# MegaShieldTrio.net
KiCad netlist of a schematic drawn in EAGLE
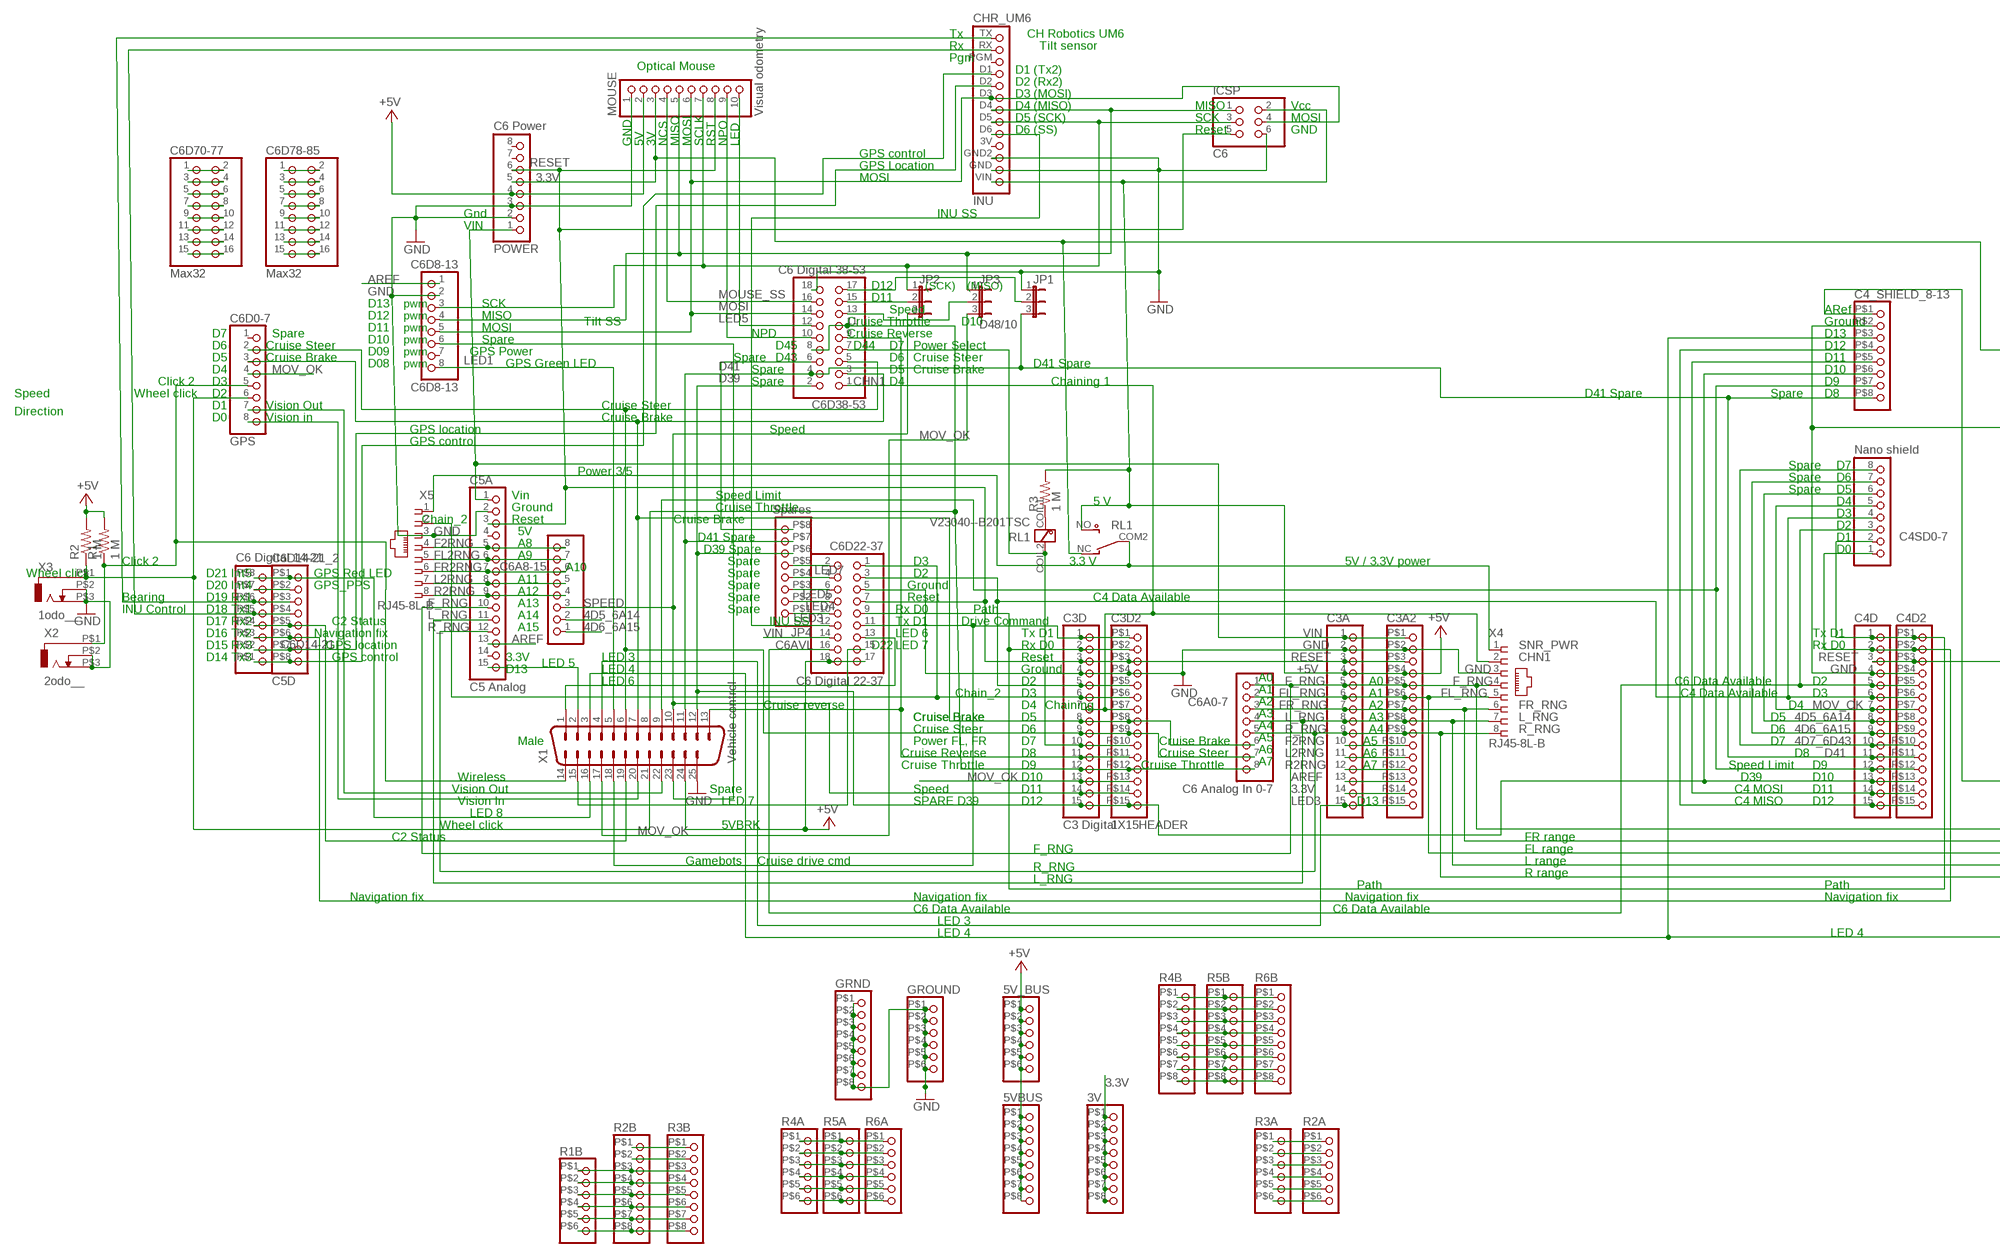
[diagram p0: schematic, sheet 1, part 1 of 2]
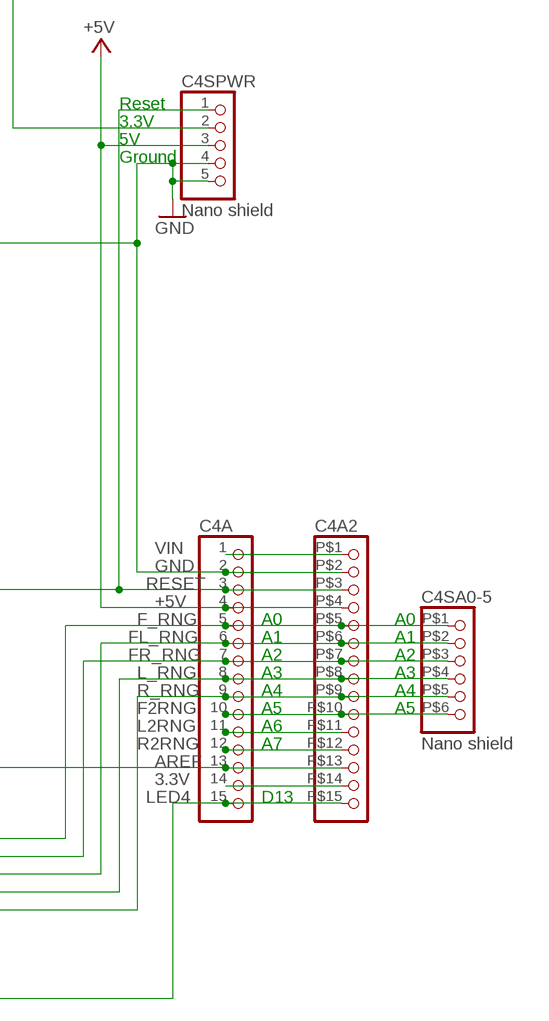
[diagram p1: schematic, sheet 1, part 2 of 2]

(export (version "E")
  (design (tool "Eeschema 10.0.6"))
  (components
    (comp (ref "3V")
      (value "PINHD-1X8SMALL8")
      (footprint "eagle-import:1X8HEADER")
      (libsource (lib "eagle-import") (part "PINHD-1X8SMALL8"))
    )
    (comp (ref "5VBUS")
      (value "PINHD-1X8SMALL8")
      (footprint "eagle-import:1X8HEADER")
      (libsource (lib "eagle-import") (part "PINHD-1X8SMALL8"))
    )
    (comp (ref "5V_BUS")
      (value "1X6HEADER")
      (footprint "eagle-import:1X6HEADER")
      (libsource (lib "eagle-import") (part "1X6HEADER"))
    )
    (comp (ref "C3A")
      (value "PINHD-1X15")
      (footprint "eagle-import:1X15")
      (libsource (lib "eagle-import") (part "PINHD-1X15"))
    )
    (comp (ref "C3A2")
      (value "1X15HEADER")
      (footprint "eagle-import:1X15HEADER")
      (libsource (lib "eagle-import") (part "1X15HEADER"))
    )
    (comp (ref "C3D")
      (value "C3 Digital")
      (footprint "eagle-import:1X15")
      (libsource (lib "eagle-import") (part "PINHD-1X15"))
    )
    (comp (ref "C3D2")
      (value "1X15HEADER")
      (footprint "eagle-import:1X15HEADER")
      (libsource (lib "eagle-import") (part "1X15HEADER"))
    )
    (comp (ref "C4A")
      (value "PINHD-1X15")
      (footprint "eagle-import:1X15")
      (libsource (lib "eagle-import") (part "PINHD-1X15"))
    )
    (comp (ref "C4A2")
      (value "1X15HEADER")
      (footprint "eagle-import:1X15HEADER")
      (libsource (lib "eagle-import") (part "1X15HEADER"))
    )
    (comp (ref "C4D")
      (value "PINHD-1X15")
      (footprint "eagle-import:1X15")
      (libsource (lib "eagle-import") (part "PINHD-1X15"))
    )
    (comp (ref "C4D2")
      (value "1X15HEADER")
      (footprint "eagle-import:1X15HEADER")
      (libsource (lib "eagle-import") (part "1X15HEADER"))
    )
    (comp (ref "C4SA0-5")
      (value "Nano shield")
      (footprint "eagle-import:1X6HEADER")
      (libsource (lib "eagle-import") (part "1X6HEADER"))
    )
    (comp (ref "C4SD0-7")
      (value "Nano shield")
      (footprint "eagle-import:1X08")
      (libsource (lib "eagle-import") (part "pinhead_PINHD-1X8"))
    )
    (comp (ref "C4SPWR")
      (value "Nano shield")
      (footprint "eagle-import:1X05")
      (libsource (lib "eagle-import") (part "PINHD-1X5"))
    )
    (comp (ref "C4_SHIELD_8-13")
      (value "PINHD-1X8SMALL8")
      (footprint "eagle-import:1X8HEADER")
      (libsource (lib "eagle-import") (part "PINHD-1X8SMALL8"))
    )
    (comp (ref "C5A")
      (value "C5 Analog")
      (footprint "eagle-import:1X15")
      (libsource (lib "eagle-import") (part "PINHD-1X15"))
    )
    (comp (ref "C6A0-7")
      (value "C6 Analog In 0-7")
      (footprint "eagle-import:1X08")
      (libsource (lib "eagle-import") (part "pinhead_PINHD-1X8"))
    )
    (comp (ref "C6A8-15")
      (value "PINHD-1X8")
      (footprint "eagle-import:1X08")
      (libsource (lib "eagle-import") (part "pinhead_PINHD-1X8"))
    )
    (comp (ref "C6D0-7")
      (value "GPS")
      (footprint "eagle-import:1X08")
      (libsource (lib "eagle-import") (part "pinhead_PINHD-1X8"))
    )
    (comp (ref "C6D8-13")
      (value "C6D8-13")
      (footprint "eagle-import:1X08")
      (libsource (lib "eagle-import") (part "pinhead_PINHD-1X8"))
    )
    (comp (ref "C6D14-21")
      (value "C6 Digital 14-21")
      (footprint "eagle-import:1X8HEADER")
      (libsource (lib "eagle-import") (part "PINHD-1X8SMALL8"))
    )
    (comp (ref "C6D14-21_2")
      (value "C5D")
      (footprint "eagle-import:1X8HEADER")
      (libsource (lib "eagle-import") (part "PINHD-1X8SMALL8"))
    )
    (comp (ref "C6D22-37")
      (value "C6 Digital 22-37")
      (footprint "eagle-import:2X09")
      (libsource (lib "eagle-import") (part "PINHD-2X9"))
    )
    (comp (ref "C6D38-53")
      (value "C6 Digital 38-53")
      (footprint "eagle-import:2X09")
      (libsource (lib "eagle-import") (part "PINHD-2X9"))
    )
    (comp (ref "C6D70-77")
      (value "Max32")
      (footprint "eagle-import:2X08")
      (libsource (lib "eagle-import") (part "PINHD-2X8"))
    )
    (comp (ref "C6D78-85")
      (value "Max32")
      (footprint "eagle-import:2X08")
      (libsource (lib "eagle-import") (part "PINHD-2X8"))
    )
    (comp (ref "GRND")
      (value "PINHD-1X8SMALL8")
      (footprint "eagle-import:1X8HEADER")
      (libsource (lib "eagle-import") (part "PINHD-1X8SMALL8"))
    )
    (comp (ref "GROUND")
      (value "1X6HEADER")
      (footprint "eagle-import:1X6HEADER")
      (libsource (lib "eagle-import") (part "1X6HEADER"))
    )
    (comp (ref "ICSP")
      (value "C6")
      (footprint "eagle-import:2X03")
      (libsource (lib "eagle-import") (part "PINHD-2X3"))
    )
    (comp (ref "INU")
      (value "CHR_UM6")
      (footprint "eagle-import:CHR_UM6")
      (libsource (lib "eagle-import") (part "CHR_UM6"))
    )
    (comp (ref "JP1")
      (value "JP2E")
      (footprint "eagle-import:JP2")
      (libsource (lib "eagle-import") (part "JP2E"))
    )
    (comp (ref "JP2")
      (value "JP2E")
      (footprint "eagle-import:JP2")
      (libsource (lib "eagle-import") (part "JP2E"))
    )
    (comp (ref "JP3")
      (value "D48/10")
      (footprint "eagle-import:JP2")
      (libsource (lib "eagle-import") (part "JP2E"))
    )
    (comp (ref "JP4")
      (value "Spares")
      (footprint "eagle-import:1X8HEADER")
      (libsource (lib "eagle-import") (part "PINHD-1X8SMALL8"))
    )
    (comp (ref "MOUSE")
      (value "Visual odometry")
      (footprint "eagle-import:1X10")
      (libsource (lib "eagle-import") (part "PINHD-1X10"))
    )
    (comp (ref "POWER")
      (value "C6 Power")
      (footprint "eagle-import:1X08")
      (libsource (lib "eagle-import") (part "pinhead_PINHD-1X8"))
    )
    (comp (ref "R1")
      (value "1 M")
      (footprint "eagle-import:0207_10")
      (libsource (lib "eagle-import") (part "R-US_0207/10"))
    )
    (comp (ref "R1B")
      (value "1X6HEADER")
      (footprint "eagle-import:1X6HEADER")
      (libsource (lib "eagle-import") (part "1X6HEADER"))
    )
    (comp (ref "R2")
      (value "1 M")
      (footprint "eagle-import:0207_10")
      (libsource (lib "eagle-import") (part "R-US_0207/10"))
    )
    (comp (ref "R2A")
      (value "1X6HEADER")
      (footprint "eagle-import:1X6HEADER")
      (libsource (lib "eagle-import") (part "1X6HEADER"))
    )
    (comp (ref "R2B")
      (value "PINHD-1X8SMALL8")
      (footprint "eagle-import:1X8HEADER")
      (libsource (lib "eagle-import") (part "PINHD-1X8SMALL8"))
    )
    (comp (ref "R3")
      (value "1 M")
      (footprint "eagle-import:0207_10")
      (libsource (lib "eagle-import") (part "R-US_0207/10"))
    )
    (comp (ref "R3A")
      (value "1X6HEADER")
      (footprint "eagle-import:1X6HEADER")
      (libsource (lib "eagle-import") (part "1X6HEADER"))
    )
    (comp (ref "R3B")
      (value "PINHD-1X8SMALL8")
      (footprint "eagle-import:1X8HEADER")
      (libsource (lib "eagle-import") (part "PINHD-1X8SMALL8"))
    )
    (comp (ref "R4A")
      (value "1X6HEADER")
      (footprint "eagle-import:1X6HEADER")
      (libsource (lib "eagle-import") (part "1X6HEADER"))
    )
    (comp (ref "R4B")
      (value "PINHD-1X8SMALL8")
      (footprint "eagle-import:1X8HEADER")
      (libsource (lib "eagle-import") (part "PINHD-1X8SMALL8"))
    )
    (comp (ref "R5A")
      (value "1X6HEADER")
      (footprint "eagle-import:1X6HEADER")
      (libsource (lib "eagle-import") (part "1X6HEADER"))
    )
    (comp (ref "R5B")
      (value "PINHD-1X8SMALL8")
      (footprint "eagle-import:1X8HEADER")
      (libsource (lib "eagle-import") (part "PINHD-1X8SMALL8"))
    )
    (comp (ref "R6A")
      (value "1X6HEADER")
      (footprint "eagle-import:1X6HEADER")
      (libsource (lib "eagle-import") (part "1X6HEADER"))
    )
    (comp (ref "R6B")
      (value "PINHD-1X8SMALL8")
      (footprint "eagle-import:1X8HEADER")
      (libsource (lib "eagle-import") (part "PINHD-1X8SMALL8"))
    )
    (comp (ref "RL1")
      (value "V23040--B201TSC")
      (footprint "eagle-import:TSC-112L3H")
      (libsource (lib "eagle-import") (part "V23040--B201TSC"))
    )
    (comp (ref "X1")
      (value "Vehicle control")
      (footprint "eagle-import:M25H")
      (libsource (lib "eagle-import") (part "M25H"))
    )
    (comp (ref "X2")
      (value "2odo__")
      (footprint "eagle-import:ODO_JACK")
      (libsource (lib "eagle-import") (part "ODO_JACK"))
    )
    (comp (ref "X3")
      (value "1odo__")
      (footprint "eagle-import:ODO_JACK")
      (libsource (lib "eagle-import") (part "ODO_JACK"))
    )
    (comp (ref "X4")
      (value "RJ45-8L-B")
      (footprint "eagle-import:RJ45-NO-SHIELD")
      (fields (field (name "MF") "TYCO ELECTRONICS"))
      (libsource (lib "eagle-import") (part "RJ45-8L-B"))
    )
    (comp (ref "X5")
      (value "RJ45-8L-B")
      (footprint "eagle-import:RJ45-NO-SHIELD")
      (fields (field (name "MF") "TYCO ELECTRONICS"))
      (libsource (lib "eagle-import") (part "RJ45-8L-B"))
    )
  )
  (nets
    (net (code "1") (name "+5V") (class "Default")
      (node (ref "5VBUS") (pin "P$1") (pinfunction "1_P$1") (pintype "passive"))
      (node (ref "5VBUS") (pin "P$2") (pinfunction "2_P$2") (pintype "passive"))
      (node (ref "5VBUS") (pin "P$3") (pinfunction "3_P$3") (pintype "passive"))
      (node (ref "5VBUS") (pin "P$4") (pinfunction "4_P$4") (pintype "passive"))
      (node (ref "5VBUS") (pin "P$5") (pinfunction "5_P$5") (pintype "passive"))
      (node (ref "5VBUS") (pin "P$6") (pinfunction "6_P$6") (pintype "passive"))
      (node (ref "5VBUS") (pin "P$7") (pinfunction "7_P$7") (pintype "passive"))
      (node (ref "5VBUS") (pin "P$8") (pinfunction "8_P$8") (pintype "passive"))
      (node (ref "5V_BUS") (pin "P$1") (pinfunction "1_P$1") (pintype "passive"))
      (node (ref "5V_BUS") (pin "P$2") (pinfunction "2_P$2") (pintype "passive"))
      (node (ref "5V_BUS") (pin "P$3") (pinfunction "3_P$3") (pintype "passive"))
      (node (ref "5V_BUS") (pin "P$4") (pinfunction "4_P$4") (pintype "passive"))
      (node (ref "5V_BUS") (pin "P$5") (pinfunction "5_P$5") (pintype "passive"))
      (node (ref "5V_BUS") (pin "P$6") (pinfunction "6_P$6") (pintype "passive"))
      (node (ref "C3A") (pin "4") (pinfunction "4_4") (pintype "passive"))
      (node (ref "C3A2") (pin "P$4") (pinfunction "4_P$4") (pintype "passive"))
      (node (ref "C4A") (pin "4") (pinfunction "4_4") (pintype "passive"))
      (node (ref "C4A2") (pin "P$4") (pinfunction "4_P$4") (pintype "passive"))
      (node (ref "C4SPWR") (pin "3") (pinfunction "3_3") (pintype "passive"))
      (node (ref "C6D22-37") (pin "17") (pinfunction "17_17") (pintype "passive"))
      (node (ref "C6D22-37") (pin "18") (pinfunction "18_18") (pintype "passive"))
      (node (ref "ICSP") (pin "2") (pinfunction "2_2") (pintype "passive"))
      (node (ref "INU") (pin "VIN") (pinfunction "1_VIN") (pintype "passive"))
      (node (ref "MOUSE") (pin "2") (pinfunction "2_2") (pintype "passive"))
      (node (ref "POWER") (pin "4") (pinfunction "4_4") (pintype "passive"))
      (node (ref "R1") (pin "2") (pinfunction "2_2") (pintype "passive"))
      (node (ref "R2") (pin "2") (pinfunction "2_2") (pintype "passive"))
      (node (ref "R3") (pin "2") (pinfunction "2_2") (pintype "passive"))
      (node (ref "RL1") (pin "NO") (pinfunction "6_NO") (pintype "passive"))
      (node (ref "X1") (pin "24") (pinfunction "24_24") (pintype "passive"))
    )
    (net (code "2") (name "/3.3V") (class "Default")
      (node (ref "3V") (pin "P$1") (pinfunction "1_P$1") (pintype "passive"))
      (node (ref "3V") (pin "P$2") (pinfunction "2_P$2") (pintype "passive"))
      (node (ref "3V") (pin "P$3") (pinfunction "3_P$3") (pintype "passive"))
      (node (ref "3V") (pin "P$4") (pinfunction "4_P$4") (pintype "passive"))
      (node (ref "3V") (pin "P$5") (pinfunction "5_P$5") (pintype "passive"))
      (node (ref "3V") (pin "P$6") (pinfunction "6_P$6") (pintype "passive"))
      (node (ref "3V") (pin "P$7") (pinfunction "7_P$7") (pintype "passive"))
      (node (ref "3V") (pin "P$8") (pinfunction "8_P$8") (pintype "passive"))
      (node (ref "C3A") (pin "14") (pinfunction "14_14") (pintype "passive"))
      (node (ref "C3A2") (pin "P$14") (pinfunction "14_P$14") (pintype "passive"))
      (node (ref "C4A") (pin "14") (pinfunction "14_14") (pintype "passive"))
      (node (ref "C4A2") (pin "P$14") (pinfunction "14_P$14") (pintype "passive"))
      (node (ref "C4SPWR") (pin "2") (pinfunction "2_2") (pintype "passive"))
      (node (ref "MOUSE") (pin "3") (pinfunction "3_3") (pintype "passive"))
      (node (ref "POWER") (pin "5") (pinfunction "5_5") (pintype "passive"))
      (node (ref "RL1") (pin "NC") (pinfunction "4_NC") (pintype "passive"))
    )
    (net (code "3") (name "/4D5_6A14") (class "Default")
      (node (ref "C4D") (pin "8") (pinfunction "8_8") (pintype "passive"))
      (node (ref "C4D2") (pin "P$8") (pinfunction "8_P$8") (pintype "passive"))
      (node (ref "C4SD0-7") (pin "6") (pinfunction "6_6") (pintype "passive"))
      (node (ref "C6A8-15") (pin "2") (pinfunction "2_2") (pintype "passive"))
    )
    (net (code "4") (name "/4D6_6A15") (class "Default")
      (node (ref "C4D") (pin "9") (pinfunction "9_9") (pintype "passive"))
      (node (ref "C4D2") (pin "P$9") (pinfunction "9_P$9") (pintype "passive"))
      (node (ref "C4SD0-7") (pin "7") (pinfunction "7_7") (pintype "passive"))
      (node (ref "C6A8-15") (pin "1") (pinfunction "1_1") (pintype "passive"))
    )
    (net (code "5") (name "/4D7_6D43") (class "Default")
      (node (ref "C4D") (pin "10") (pinfunction "10_10") (pintype "passive"))
      (node (ref "C4D2") (pin "P$10") (pinfunction "10_P$10") (pintype "passive"))
      (node (ref "C4SD0-7") (pin "8") (pinfunction "8_8") (pintype "passive"))
    )
    (net (code "6") (name "/AREF") (class "Default")
      (node (ref "C3A") (pin "13") (pinfunction "13_13") (pintype "passive"))
      (node (ref "C3A2") (pin "P$13") (pinfunction "13_P$13") (pintype "passive"))
      (node (ref "C4A") (pin "13") (pinfunction "13_13") (pintype "passive"))
      (node (ref "C4A2") (pin "P$13") (pinfunction "13_P$13") (pintype "passive"))
      (node (ref "C4_SHIELD_8-13") (pin "P$1") (pinfunction "1_P$1") (pintype "passive"))
      (node (ref "C5A") (pin "13") (pinfunction "13_13") (pintype "passive"))
      (node (ref "C6D8-13") (pin "1") (pinfunction "1_1") (pintype "passive"))
    )
    (net (code "7") (name "/C6AVL") (class "Default")
      (node (ref "C4D") (pin "5") (pinfunction "5_5") (pintype "passive"))
      (node (ref "C4D2") (pin "P$5") (pinfunction "5_P$5") (pintype "passive"))
      (node (ref "C4SD0-7") (pin "3") (pinfunction "3_3") (pintype "passive"))
      (node (ref "C6D22-37") (pin "16") (pinfunction "16_16") (pintype "passive"))
    )
    (net (code "8") (name "/CHN1") (class "Default")
      (node (ref "C3D") (pin "7") (pinfunction "7_7") (pintype "passive"))
      (node (ref "C3D2") (pin "P$7") (pinfunction "7_P$7") (pintype "passive"))
      (node (ref "C6D38-53") (pin "1") (pinfunction "1_1") (pintype "passive"))
      (node (ref "X4") (pin "2") (pinfunction "2_2") (pintype "passive"))
    )
    (net (code "9") (name "/D39") (class "Default")
      (node (ref "C3D") (pin "15") (pinfunction "15_15") (pintype "passive"))
      (node (ref "C3D2") (pin "P$15") (pinfunction "15_P$15") (pintype "passive"))
      (node (ref "C4D") (pin "13") (pinfunction "13_13") (pintype "passive"))
      (node (ref "C4D2") (pin "P$13") (pinfunction "13_P$13") (pintype "passive"))
      (node (ref "C4_SHIELD_8-13") (pin "P$6") (pinfunction "6_P$6") (pintype "passive"))
      (node (ref "C6D38-53") (pin "2") (pinfunction "2_2") (pintype "passive"))
      (node (ref "JP4") (pin "P$6") (pinfunction "6_P$6") (pintype "passive"))
      (node (ref "X1") (pin "12") (pinfunction "12_12") (pintype "passive"))
    )
    (net (code "10") (name "/D41") (class "Default")
      (node (ref "C4D") (pin "11") (pinfunction "11_11") (pintype "passive"))
      (node (ref "C4D2") (pin "P$11") (pinfunction "11_P$11") (pintype "passive"))
      (node (ref "C4_SHIELD_8-13") (pin "P$8") (pinfunction "8_P$8") (pintype "passive"))
      (node (ref "C6D38-53") (pin "4") (pinfunction "4_4") (pintype "passive"))
      (node (ref "JP1") (pin "3") (pinfunction "3_3") (pintype "passive"))
      (node (ref "JP4") (pin "P$7") (pinfunction "7_P$7") (pintype "passive"))
      (node (ref "X1") (pin "11") (pinfunction "11_11") (pintype "passive"))
    )
    (net (code "11") (name "/F2RNG") (class "Default")
      (node (ref "C3A") (pin "10") (pinfunction "10_10") (pintype "passive"))
      (node (ref "C3A2") (pin "P$10") (pinfunction "10_P$10") (pintype "passive"))
      (node (ref "C4A") (pin "10") (pinfunction "10_10") (pintype "passive"))
      (node (ref "C4A2") (pin "P$10") (pinfunction "10_P$10") (pintype "passive"))
      (node (ref "C4SA0-5") (pin "P$6") (pinfunction "6_P$6") (pintype "passive"))
      (node (ref "C5A") (pin "5") (pinfunction "5_5") (pintype "passive"))
      (node (ref "C6A8-15") (pin "8") (pinfunction "8_8") (pintype "passive"))
      (node (ref "X5") (pin "4") (pinfunction "4_4") (pintype "passive"))
    )
    (net (code "12") (name "/FL2RNG") (class "Default")
      (node (ref "C5A") (pin "6") (pinfunction "6_6") (pintype "passive"))
      (node (ref "C6A8-15") (pin "7") (pinfunction "7_7") (pintype "passive"))
      (node (ref "X5") (pin "5") (pinfunction "5_5") (pintype "passive"))
    )
    (net (code "13") (name "/FL_RNG") (class "Default")
      (node (ref "C3A") (pin "6") (pinfunction "6_6") (pintype "passive"))
      (node (ref "C3A2") (pin "P$6") (pinfunction "6_P$6") (pintype "passive"))
      (node (ref "C4A") (pin "6") (pinfunction "6_6") (pintype "passive"))
      (node (ref "C4A2") (pin "P$6") (pinfunction "6_P$6") (pintype "passive"))
      (node (ref "C4SA0-5") (pin "P$2") (pinfunction "2_P$2") (pintype "passive"))
      (node (ref "C6A0-7") (pin "2") (pinfunction "2_2") (pintype "passive"))
      (node (ref "X4") (pin "5") (pinfunction "5_5") (pintype "passive"))
    )
    (net (code "14") (name "/FR2RNG") (class "Default")
      (node (ref "C5A") (pin "7") (pinfunction "7_7") (pintype "passive"))
      (node (ref "C6A8-15") (pin "6") (pinfunction "6_6") (pintype "passive"))
      (node (ref "X5") (pin "6") (pinfunction "6_6") (pintype "passive"))
    )
    (net (code "15") (name "/FR_RNG") (class "Default")
      (node (ref "C3A") (pin "7") (pinfunction "7_7") (pintype "passive"))
      (node (ref "C3A2") (pin "P$7") (pinfunction "7_P$7") (pintype "passive"))
      (node (ref "C4A") (pin "7") (pinfunction "7_7") (pintype "passive"))
      (node (ref "C4A2") (pin "P$7") (pinfunction "7_P$7") (pintype "passive"))
      (node (ref "C4SA0-5") (pin "P$3") (pinfunction "3_P$3") (pintype "passive"))
      (node (ref "C6A0-7") (pin "3") (pinfunction "3_3") (pintype "passive"))
      (node (ref "X4") (pin "6") (pinfunction "6_6") (pintype "passive"))
    )
    (net (code "16") (name "/F_RNG") (class "Default")
      (node (ref "C3A") (pin "5") (pinfunction "5_5") (pintype "passive"))
      (node (ref "C3A2") (pin "P$5") (pinfunction "5_P$5") (pintype "passive"))
      (node (ref "C4A") (pin "5") (pinfunction "5_5") (pintype "passive"))
      (node (ref "C4A2") (pin "P$5") (pinfunction "5_P$5") (pintype "passive"))
      (node (ref "C4SA0-5") (pin "P$1") (pinfunction "1_P$1") (pintype "passive"))
      (node (ref "C5A") (pin "10") (pinfunction "10_10") (pintype "passive"))
      (node (ref "C6A0-7") (pin "1") (pinfunction "1_1") (pintype "passive"))
      (node (ref "X4") (pin "4") (pinfunction "4_4") (pintype "passive"))
    )
    (net (code "17") (name "/L2RNG") (class "Default")
      (node (ref "C3A") (pin "11") (pinfunction "11_11") (pintype "passive"))
      (node (ref "C3A2") (pin "P$11") (pinfunction "11_P$11") (pintype "passive"))
      (node (ref "C4A") (pin "11") (pinfunction "11_11") (pintype "passive"))
      (node (ref "C4A2") (pin "P$11") (pinfunction "11_P$11") (pintype "passive"))
      (node (ref "C5A") (pin "8") (pinfunction "8_8") (pintype "passive"))
      (node (ref "C6A8-15") (pin "5") (pinfunction "5_5") (pintype "passive"))
      (node (ref "X5") (pin "7") (pinfunction "7_7") (pintype "passive"))
    )
    (net (code "18") (name "/LED1") (class "Default")
      (node (ref "C6D8-13") (pin "8") (pinfunction "8_8") (pintype "passive"))
      (node (ref "X1") (pin "5") (pinfunction "5_5") (pintype "passive"))
    )
    (net (code "19") (name "/LED3") (class "Default")
      (node (ref "C3A") (pin "15") (pinfunction "15_15") (pintype "passive"))
      (node (ref "C3A2") (pin "P$15") (pinfunction "15_P$15") (pintype "passive"))
      (node (ref "X1") (pin "4") (pinfunction "4_4") (pintype "passive"))
    )
    (net (code "20") (name "/LED4") (class "Default")
      (node (ref "C4A") (pin "15") (pinfunction "15_15") (pintype "passive"))
      (node (ref "C4A2") (pin "P$15") (pinfunction "15_P$15") (pintype "passive"))
      (node (ref "C4_SHIELD_8-13") (pin "P$3") (pinfunction "3_P$3") (pintype "passive"))
      (node (ref "X1") (pin "3") (pinfunction "3_3") (pintype "passive"))
    )
    (net (code "21") (name "/LED5") (class "Default")
      (node (ref "C5A") (pin "15") (pinfunction "15_15") (pintype "passive"))
      (node (ref "C6D38-53") (pin "12") (pinfunction "12_12") (pintype "passive"))
      (node (ref "MOUSE") (pin "10") (pinfunction "10_10") (pintype "passive"))
      (node (ref "X1") (pin "2") (pinfunction "2_2") (pintype "passive"))
    )
    (net (code "22") (name "/LED7") (class "Default")
      (node (ref "C6D22-37") (pin "15") (pinfunction "15_15") (pintype "passive"))
      (node (ref "X1") (pin "15") (pinfunction "15_15") (pintype "passive"))
    )
    (net (code "23") (name "/L_RNG") (class "Default")
      (node (ref "C3A") (pin "8") (pinfunction "8_8") (pintype "passive"))
      (node (ref "C3A2") (pin "P$8") (pinfunction "8_P$8") (pintype "passive"))
      (node (ref "C4A") (pin "8") (pinfunction "8_8") (pintype "passive"))
      (node (ref "C4A2") (pin "P$8") (pinfunction "8_P$8") (pintype "passive"))
      (node (ref "C4SA0-5") (pin "P$4") (pinfunction "4_P$4") (pintype "passive"))
      (node (ref "C5A") (pin "11") (pinfunction "11_11") (pintype "passive"))
      (node (ref "C6A0-7") (pin "4") (pinfunction "4_4") (pintype "passive"))
      (node (ref "X4") (pin "7") (pinfunction "7_7") (pintype "passive"))
    )
    (net (code "24") (name "/MOSI") (class "Default")
      (node (ref "C6D38-53") (pin "14") (pinfunction "14_14") (pintype "passive"))
      (node (ref "C6D8-13") (pin "5") (pinfunction "5_5") (pintype "passive"))
      (node (ref "ICSP") (pin "4") (pinfunction "4_4") (pintype "passive"))
      (node (ref "INU") (pin "D3") (pinfunction "8_D3") (pintype "passive"))
      (node (ref "MOUSE") (pin "6") (pinfunction "6_6") (pintype "passive"))
    )
    (net (code "25") (name "/MOUSE_SS") (class "Default")
      (node (ref "C6D38-53") (pin "16") (pinfunction "16_16") (pintype "passive"))
      (node (ref "MOUSE") (pin "4") (pinfunction "4_4") (pintype "passive"))
    )
    (net (code "26") (name "/MOV_OK") (class "Default")
      (node (ref "C3D") (pin "13") (pinfunction "13_13") (pintype "passive"))
      (node (ref "C3D2") (pin "P$13") (pinfunction "13_P$13") (pintype "passive"))
      (node (ref "C4D") (pin "7") (pinfunction "7_7") (pintype "passive"))
      (node (ref "C4D2") (pin "P$7") (pinfunction "7_P$7") (pintype "passive"))
      (node (ref "C4SD0-7") (pin "5") (pinfunction "5_5") (pintype "passive"))
      (node (ref "C6D0-7") (pin "4") (pinfunction "4_4") (pintype "passive"))
      (node (ref "JP3") (pin "3") (pinfunction "3_3") (pintype "passive"))
      (node (ref "X1") (pin "17") (pinfunction "17_17") (pintype "passive"))
    )
    (net (code "27") (name "/R2RNG") (class "Default")
      (node (ref "C3A") (pin "12") (pinfunction "12_12") (pintype "passive"))
      (node (ref "C3A2") (pin "P$12") (pinfunction "12_P$12") (pintype "passive"))
      (node (ref "C4A") (pin "12") (pinfunction "12_12") (pintype "passive"))
      (node (ref "C4A2") (pin "P$12") (pinfunction "12_P$12") (pintype "passive"))
      (node (ref "C5A") (pin "9") (pinfunction "9_9") (pintype "passive"))
      (node (ref "C6A8-15") (pin "4") (pinfunction "4_4") (pintype "passive"))
      (node (ref "X5") (pin "8") (pinfunction "8_8") (pintype "passive"))
    )
    (net (code "28") (name "/RESET") (class "Default")
      (node (ref "C3A") (pin "3") (pinfunction "3_3") (pintype "passive"))
      (node (ref "C3A2") (pin "P$3") (pinfunction "3_P$3") (pintype "passive"))
      (node (ref "C3D") (pin "3") (pinfunction "3_3") (pintype "passive"))
      (node (ref "C3D2") (pin "P$3") (pinfunction "3_P$3") (pintype "passive"))
      (node (ref "C4A") (pin "3") (pinfunction "3_3") (pintype "passive"))
      (node (ref "C4A2") (pin "P$3") (pinfunction "3_P$3") (pintype "passive"))
      (node (ref "C4D") (pin "3") (pinfunction "3_3") (pintype "passive"))
      (node (ref "C4D2") (pin "P$3") (pinfunction "3_P$3") (pintype "passive"))
      (node (ref "C4SPWR") (pin "1") (pinfunction "1_1") (pintype "passive"))
      (node (ref "C5A") (pin "3") (pinfunction "3_3") (pintype "passive"))
      (node (ref "C6D22-37") (pin "7") (pinfunction "7_7") (pintype "passive"))
      (node (ref "ICSP") (pin "5") (pinfunction "5_5") (pintype "passive"))
      (node (ref "MOUSE") (pin "8") (pinfunction "8_8") (pintype "passive"))
      (node (ref "POWER") (pin "6") (pinfunction "6_6") (pintype "passive"))
    )
    (net (code "29") (name "/R_RNG") (class "Default")
      (node (ref "C3A") (pin "9") (pinfunction "9_9") (pintype "passive"))
      (node (ref "C3A2") (pin "P$9") (pinfunction "9_P$9") (pintype "passive"))
      (node (ref "C4A") (pin "9") (pinfunction "9_9") (pintype "passive"))
      (node (ref "C4A2") (pin "P$9") (pinfunction "9_P$9") (pintype "passive"))
      (node (ref "C4SA0-5") (pin "P$5") (pinfunction "5_P$5") (pintype "passive"))
      (node (ref "C5A") (pin "12") (pinfunction "12_12") (pintype "passive"))
      (node (ref "C6A0-7") (pin "5") (pinfunction "5_5") (pintype "passive"))
      (node (ref "X4") (pin "8") (pinfunction "8_8") (pintype "passive"))
    )
    (net (code "30") (name "/SNR_PWR") (class "Default")
      (node (ref "RL1") (pin "COM2") (pinfunction "5_COM2") (pintype "passive"))
      (node (ref "X4") (pin "1") (pinfunction "1_1") (pintype "passive"))
      (node (ref "X5") (pin "1") (pinfunction "1_1") (pintype "passive"))
    )
    (net (code "31") (name "/SPEED") (class "Default")
      (node (ref "C3D") (pin "14") (pinfunction "14_14") (pintype "passive"))
      (node (ref "C3D2") (pin "P$14") (pinfunction "14_P$14") (pintype "passive"))
      (node (ref "C6A8-15") (pin "3") (pinfunction "3_3") (pintype "passive"))
      (node (ref "JP2") (pin "3") (pinfunction "3_3") (pintype "passive"))
      (node (ref "X1") (pin "10") (pinfunction "10_10") (pintype "passive"))
    )
    (net (code "32") (name "/VIN") (class "Default")
      (node (ref "C3A") (pin "1") (pinfunction "1_1") (pintype "passive"))
      (node (ref "C3A2") (pin "P$1") (pinfunction "1_P$1") (pintype "passive"))
      (node (ref "C4A") (pin "1") (pinfunction "1_1") (pintype "passive"))
      (node (ref "C4A2") (pin "P$1") (pinfunction "1_P$1") (pintype "passive"))
      (node (ref "C5A") (pin "1") (pinfunction "1_1") (pintype "passive"))
      (node (ref "C6D22-37") (pin "14") (pinfunction "14_14") (pintype "passive"))
      (node (ref "POWER") (pin "1") (pinfunction "1_1") (pintype "passive"))
    )
    (net (code "33") (name "GND") (class "Default")
      (node (ref "C3A") (pin "2") (pinfunction "2_2") (pintype "passive"))
      (node (ref "C3A2") (pin "P$2") (pinfunction "2_P$2") (pintype "passive"))
      (node (ref "C3D") (pin "4") (pinfunction "4_4") (pintype "passive"))
      (node (ref "C3D2") (pin "P$4") (pinfunction "4_P$4") (pintype "passive"))
      (node (ref "C4A") (pin "2") (pinfunction "2_2") (pintype "passive"))
      (node (ref "C4A2") (pin "P$2") (pinfunction "2_P$2") (pintype "passive"))
      (node (ref "C4D") (pin "4") (pinfunction "4_4") (pintype "passive"))
      (node (ref "C4D2") (pin "P$4") (pinfunction "4_P$4") (pintype "passive"))
      (node (ref "C4SPWR") (pin "4") (pinfunction "4_4") (pintype "passive"))
      (node (ref "C4SPWR") (pin "5") (pinfunction "5_5") (pintype "passive"))
      (node (ref "C4_SHIELD_8-13") (pin "P$2") (pinfunction "2_P$2") (pintype "passive"))
      (node (ref "C5A") (pin "2") (pinfunction "2_2") (pintype "passive"))
      (node (ref "C6D22-37") (pin "5") (pinfunction "5_5") (pintype "passive"))
      (node (ref "C6D38-53") (pin "18") (pinfunction "18_18") (pintype "passive"))
      (node (ref "C6D8-13") (pin "2") (pinfunction "2_2") (pintype "passive"))
      (node (ref "GRND") (pin "P$1") (pinfunction "1_P$1") (pintype "passive"))
      (node (ref "GRND") (pin "P$2") (pinfunction "2_P$2") (pintype "passive"))
      (node (ref "GRND") (pin "P$3") (pinfunction "3_P$3") (pintype "passive"))
      (node (ref "GRND") (pin "P$4") (pinfunction "4_P$4") (pintype "passive"))
      (node (ref "GRND") (pin "P$5") (pinfunction "5_P$5") (pintype "passive"))
      (node (ref "GRND") (pin "P$6") (pinfunction "6_P$6") (pintype "passive"))
      (node (ref "GRND") (pin "P$7") (pinfunction "7_P$7") (pintype "passive"))
      (node (ref "GRND") (pin "P$8") (pinfunction "8_P$8") (pintype "passive"))
      (node (ref "GROUND") (pin "P$1") (pinfunction "1_P$1") (pintype "passive"))
      (node (ref "GROUND") (pin "P$2") (pinfunction "2_P$2") (pintype "passive"))
      (node (ref "GROUND") (pin "P$3") (pinfunction "3_P$3") (pintype "passive"))
      (node (ref "GROUND") (pin "P$4") (pinfunction "4_P$4") (pintype "passive"))
      (node (ref "GROUND") (pin "P$5") (pinfunction "5_P$5") (pintype "passive"))
      (node (ref "GROUND") (pin "P$6") (pinfunction "6_P$6") (pintype "passive"))
      (node (ref "ICSP") (pin "6") (pinfunction "6_6") (pintype "passive"))
      (node (ref "INU") (pin "GND") (pinfunction "2_GND") (pintype "passive"))
      (node (ref "INU") (pin "GND2") (pinfunction "3_GND2") (pintype "passive"))
      (node (ref "JP1") (pin "1") (pinfunction "1_1") (pintype "passive"))
      (node (ref "MOUSE") (pin "1") (pinfunction "1_1") (pintype "passive"))
      (node (ref "POWER") (pin "2") (pinfunction "2_2") (pintype "passive"))
      (node (ref "POWER") (pin "3") (pinfunction "3_3") (pintype "passive"))
      (node (ref "X1") (pin "25") (pinfunction "25_25") (pintype "passive"))
      (node (ref "X2") (pin "P$2") (pinfunction "2_P$2") (pintype "passive"))
      (node (ref "X2") (pin "P$3") (pinfunction "3_P$3") (pintype "passive"))
      (node (ref "X3") (pin "P$2") (pinfunction "2_P$2") (pintype "passive"))
      (node (ref "X3") (pin "P$3") (pinfunction "3_P$3") (pintype "passive"))
      (node (ref "X4") (pin "3") (pinfunction "3_3") (pintype "passive"))
      (node (ref "X5") (pin "3") (pinfunction "3_3") (pintype "passive"))
    )
    (net (code "34") (name "Net-(C3D2-1)") (class "Default")
      (node (ref "C3D") (pin "1") (pinfunction "1_1") (pintype "passive"))
      (node (ref "C3D2") (pin "P$1") (pinfunction "1_P$1") (pintype "passive"))
      (node (ref "C6D22-37") (pin "11") (pinfunction "11_11") (pintype "passive"))
      (node (ref "X1") (pin "18") (pinfunction "18_18") (pintype "passive"))
    )
    (net (code "35") (name "Net-(C3D2-2)") (class "Default")
      (node (ref "C3D") (pin "2") (pinfunction "2_2") (pintype "passive"))
      (node (ref "C3D2") (pin "P$2") (pinfunction "2_P$2") (pintype "passive"))
      (node (ref "C4D") (pin "1") (pinfunction "1_1") (pintype "passive"))
      (node (ref "C4D2") (pin "P$1") (pinfunction "1_P$1") (pintype "passive"))
      (node (ref "C4SD0-7") (pin "2") (pinfunction "2_2") (pintype "passive"))
      (node (ref "C6D22-37") (pin "9") (pinfunction "9_9") (pintype "passive"))
    )
    (net (code "36") (name "Net-(C3D2-5)") (class "Default")
      (node (ref "C3D") (pin "5") (pinfunction "5_5") (pintype "passive"))
      (node (ref "C3D2") (pin "P$5") (pinfunction "5_P$5") (pintype "passive"))
      (node (ref "C4D") (pin "6") (pinfunction "6_6") (pintype "passive"))
      (node (ref "C4D2") (pin "P$6") (pinfunction "6_P$6") (pintype "passive"))
      (node (ref "C4SD0-7") (pin "4") (pinfunction "4_4") (pintype "passive"))
      (node (ref "C6D22-37") (pin "3") (pinfunction "3_3") (pintype "passive"))
    )
    (net (code "37") (name "Net-(C3D2-6)") (class "Default")
      (node (ref "C3D") (pin "6") (pinfunction "6_6") (pintype "passive"))
      (node (ref "C3D2") (pin "P$6") (pinfunction "6_P$6") (pintype "passive"))
      (node (ref "C6D22-37") (pin "1") (pinfunction "1_1") (pintype "passive"))
      (node (ref "X5") (pin "2") (pinfunction "2_2") (pintype "passive"))
    )
    (net (code "38") (name "Net-(C3D2-8)") (class "Default")
      (node (ref "C3D") (pin "8") (pinfunction "8_8") (pintype "passive"))
      (node (ref "C3D2") (pin "P$8") (pinfunction "8_P$8") (pintype "passive"))
      (node (ref "C6A0-7") (pin "6") (pinfunction "6_6") (pintype "passive"))
      (node (ref "C6D0-7") (pin "3") (pinfunction "3_3") (pintype "passive"))
      (node (ref "C6D38-53") (pin "3") (pinfunction "3_3") (pintype "passive"))
      (node (ref "X1") (pin "7") (pinfunction "7_7") (pintype "passive"))
    )
    (net (code "39") (name "Net-(C3D2-9)") (class "Default")
      (node (ref "C3D") (pin "9") (pinfunction "9_9") (pintype "passive"))
      (node (ref "C3D2") (pin "P$9") (pinfunction "9_P$9") (pintype "passive"))
      (node (ref "C6A0-7") (pin "7") (pinfunction "7_7") (pintype "passive"))
      (node (ref "C6D0-7") (pin "2") (pinfunction "2_2") (pintype "passive"))
      (node (ref "C6D38-53") (pin "5") (pinfunction "5_5") (pintype "passive"))
      (node (ref "X1") (pin "6") (pinfunction "6_6") (pintype "passive"))
    )
    (net (code "40") (name "Net-(C3D2-10)") (class "Default")
      (node (ref "C3D") (pin "10") (pinfunction "10_10") (pintype "passive"))
      (node (ref "C3D2") (pin "P$10") (pinfunction "10_P$10") (pintype "passive"))
      (node (ref "C6D38-53") (pin "7") (pinfunction "7_7") (pintype "passive"))
      (node (ref "RL1") (pin "COIL2") (pinfunction "2_COIL2") (pintype "passive"))
    )
    (net (code "41") (name "Net-(C3D2-11)") (class "Default")
      (node (ref "C3D") (pin "11") (pinfunction "11_11") (pintype "passive"))
      (node (ref "C3D2") (pin "P$11") (pinfunction "11_P$11") (pintype "passive"))
      (node (ref "C6D38-53") (pin "9") (pinfunction "9_9") (pintype "passive"))
      (node (ref "X1") (pin "13") (pinfunction "13_13") (pintype "passive"))
    )
    (net (code "42") (name "Net-(C3D2-12)") (class "Default")
      (node (ref "C3D") (pin "12") (pinfunction "12_12") (pintype "passive"))
      (node (ref "C3D2") (pin "P$12") (pinfunction "12_P$12") (pintype "passive"))
      (node (ref "C6A0-7") (pin "8") (pinfunction "8_8") (pintype "passive"))
      (node (ref "C6D38-53") (pin "11") (pinfunction "11_11") (pintype "passive"))
      (node (ref "C6D38-53") (pin "8") (pinfunction "8_8") (pintype "passive"))
      (node (ref "X1") (pin "8") (pinfunction "8_8") (pintype "passive"))
    )
    (net (code "43") (name "Net-(C4D2-2)") (class "Default")
      (node (ref "C4D") (pin "2") (pinfunction "2_2") (pintype "passive"))
      (node (ref "C4D2") (pin "P$2") (pinfunction "2_P$2") (pintype "passive"))
      (node (ref "C4SD0-7") (pin "1") (pinfunction "1_1") (pintype "passive"))
      (node (ref "C6D14-21") (pin "P$3") (pinfunction "3_P$3") (pintype "passive"))
      (node (ref "C6D14-21_2") (pin "P$6") (pinfunction "6_P$6") (pintype "passive"))
    )
    (net (code "44") (name "Net-(C4D2-12)") (class "Default")
      (node (ref "C4D") (pin "12") (pinfunction "12_12") (pintype "passive"))
      (node (ref "C4D2") (pin "P$12") (pinfunction "12_P$12") (pintype "passive"))
      (node (ref "C4_SHIELD_8-13") (pin "P$7") (pinfunction "7_P$7") (pintype "passive"))
      (node (ref "X1") (pin "9") (pinfunction "9_9") (pintype "passive"))
    )
    (net (code "45") (name "Net-(C4D2-14)") (class "Default")
      (node (ref "C4D") (pin "14") (pinfunction "14_14") (pintype "passive"))
      (node (ref "C4D2") (pin "P$14") (pinfunction "14_P$14") (pintype "passive"))
      (node (ref "C4_SHIELD_8-13") (pin "P$5") (pinfunction "5_P$5") (pintype "passive"))
    )
    (net (code "46") (name "Net-(C4D2-15)") (class "Default")
      (node (ref "C4D") (pin "15") (pinfunction "15_15") (pintype "passive"))
      (node (ref "C4D2") (pin "P$15") (pinfunction "15_P$15") (pintype "passive"))
      (node (ref "C4_SHIELD_8-13") (pin "P$4") (pinfunction "4_P$4") (pintype "passive"))
    )
    (net (code "47") (name "Net-(C6D0-7-Pad7)") (class "Default")
      (node (ref "C6D0-7") (pin "7") (pinfunction "7_7") (pintype "passive"))
      (node (ref "X1") (pin "22") (pinfunction "22_22") (pintype "passive"))
    )
    (net (code "48") (name "Net-(C6D0-7-Pad8)") (class "Default")
      (node (ref "C6D0-7") (pin "8") (pinfunction "8_8") (pintype "passive"))
      (node (ref "X1") (pin "20") (pinfunction "20_20") (pintype "passive"))
    )
    (net (code "49") (name "Net-(C6D8-13-Pad6)") (class "Default")
      (node (ref "C6D8-13") (pin "6") (pinfunction "6_6") (pintype "passive"))
      (node (ref "X1") (pin "23") (pinfunction "23_23") (pintype "passive"))
    )
    (net (code "50") (name "Net-(C6D14-21-1)") (class "Default")
      (node (ref "C6D14-21") (pin "P$1") (pinfunction "1_P$1") (pintype "passive"))
      (node (ref "C6D14-21_2") (pin "P$8") (pinfunction "8_P$8") (pintype "passive"))
      (node (ref "INU") (pin "D1") (pinfunction "10_D1") (pintype "passive"))
    )
    (net (code "51") (name "Net-(C6D14-21-2)") (class "Default")
      (node (ref "C6D14-21") (pin "P$2") (pinfunction "2_P$2") (pintype "passive"))
      (node (ref "C6D14-21_2") (pin "P$7") (pinfunction "7_P$7") (pintype "passive"))
      (node (ref "INU") (pin "D2") (pinfunction "9_D2") (pintype "passive"))
    )
    (net (code "52") (name "Net-(C6D14-21-4)") (class "Default")
      (node (ref "C6D14-21") (pin "P$4") (pinfunction "4_P$4") (pintype "passive"))
      (node (ref "C6D14-21_2") (pin "P$5") (pinfunction "5_P$5") (pintype "passive"))
      (node (ref "X1") (pin "19") (pinfunction "19_19") (pintype "passive"))
    )
    (net (code "53") (name "Net-(C6D14-21-5)") (class "Default")
      (node (ref "C6D14-21") (pin "P$5") (pinfunction "5_P$5") (pintype "passive"))
      (node (ref "C6D14-21_2") (pin "P$4") (pinfunction "4_P$4") (pintype "passive"))
      (node (ref "INU") (pin "RX") (pinfunction "12_RX") (pintype "passive"))
    )
    (net (code "54") (name "Net-(C6D14-21-6)") (class "Default")
      (node (ref "C6D14-21") (pin "P$6") (pinfunction "6_P$6") (pintype "passive"))
      (node (ref "C6D14-21_2") (pin "P$3") (pinfunction "3_P$3") (pintype "passive"))
      (node (ref "INU") (pin "TX") (pinfunction "13_TX") (pintype "passive"))
    )
    (net (code "55") (name "Net-(C6D14-21-7)") (class "Default")
      (node (ref "C6D14-21") (pin "P$7") (pinfunction "7_P$7") (pintype "passive"))
      (node (ref "C6D14-21_2") (pin "P$2") (pinfunction "2_P$2") (pintype "passive"))
    )
    (net (code "56") (name "Net-(C6D14-21-8)") (class "Default")
      (node (ref "C6D14-21") (pin "P$8") (pinfunction "8_P$8") (pintype "passive"))
      (node (ref "C6D14-21_2") (pin "P$1") (pinfunction "1_P$1") (pintype "passive"))
      (node (ref "X1") (pin "16") (pinfunction "16_16") (pintype "passive"))
    )
    (net (code "57") (name "Net-(C6D22-37-Pad13)") (class "Default")
      (node (ref "C6D22-37") (pin "13") (pinfunction "13_13") (pintype "passive"))
      (node (ref "X1") (pin "1") (pinfunction "1_1") (pintype "passive"))
    )
    (net (code "58") (name "Net-(C6D38-53-Pad10)") (class "Default")
      (node (ref "C6D38-53") (pin "10") (pinfunction "10_10") (pintype "passive"))
      (node (ref "MOUSE") (pin "9") (pinfunction "9_9") (pintype "passive"))
    )
    (net (code "59") (name "Net-(C6D38-53-Pad13)") (class "Default")
      (node (ref "C6D38-53") (pin "13") (pinfunction "13_13") (pintype "passive"))
      (node (ref "JP3") (pin "2") (pinfunction "2_2") (pintype "passive"))
    )
    (net (code "60") (name "Net-(C6D38-53-Pad15)") (class "Default")
      (node (ref "C6D38-53") (pin "15") (pinfunction "15_15") (pintype "passive"))
      (node (ref "JP2") (pin "2") (pinfunction "2_2") (pintype "passive"))
    )
    (net (code "61") (name "Net-(C6D38-53-Pad17)") (class "Default")
      (node (ref "C6D38-53") (pin "17") (pinfunction "17_17") (pintype "passive"))
      (node (ref "JP1") (pin "2") (pinfunction "2_2") (pintype "passive"))
    )
    (net (code "62") (name "Net-(C6D70-77-Pad1)") (class "Default")
      (node (ref "C6D70-77") (pin "1") (pinfunction "1_1") (pintype "passive"))
      (node (ref "C6D70-77") (pin "2") (pinfunction "2_2") (pintype "passive"))
    )
    (net (code "63") (name "Net-(C6D70-77-Pad3)") (class "Default")
      (node (ref "C6D70-77") (pin "3") (pinfunction "3_3") (pintype "passive"))
      (node (ref "C6D70-77") (pin "4") (pinfunction "4_4") (pintype "passive"))
    )
    (net (code "64") (name "Net-(C6D70-77-Pad5)") (class "Default")
      (node (ref "C6D70-77") (pin "5") (pinfunction "5_5") (pintype "passive"))
      (node (ref "C6D70-77") (pin "6") (pinfunction "6_6") (pintype "passive"))
    )
    (net (code "65") (name "Net-(C6D70-77-Pad7)") (class "Default")
      (node (ref "C6D70-77") (pin "7") (pinfunction "7_7") (pintype "passive"))
      (node (ref "C6D70-77") (pin "8") (pinfunction "8_8") (pintype "passive"))
    )
    (net (code "66") (name "Net-(C6D70-77-Pad10)") (class "Default")
      (node (ref "C6D70-77") (pin "10") (pinfunction "10_10") (pintype "passive"))
      (node (ref "C6D70-77") (pin "9") (pinfunction "9_9") (pintype "passive"))
    )
    (net (code "67") (name "Net-(C6D70-77-Pad11)") (class "Default")
      (node (ref "C6D70-77") (pin "11") (pinfunction "11_11") (pintype "passive"))
      (node (ref "C6D70-77") (pin "12") (pinfunction "12_12") (pintype "passive"))
    )
    (net (code "68") (name "Net-(C6D70-77-Pad13)") (class "Default")
      (node (ref "C6D70-77") (pin "13") (pinfunction "13_13") (pintype "passive"))
      (node (ref "C6D70-77") (pin "14") (pinfunction "14_14") (pintype "passive"))
    )
    (net (code "69") (name "Net-(C6D70-77-Pad15)") (class "Default")
      (node (ref "C6D70-77") (pin "15") (pinfunction "15_15") (pintype "passive"))
      (node (ref "C6D70-77") (pin "16") (pinfunction "16_16") (pintype "passive"))
    )
    (net (code "70") (name "Net-(C6D78-85-Pad1)") (class "Default")
      (node (ref "C6D78-85") (pin "1") (pinfunction "1_1") (pintype "passive"))
      (node (ref "C6D78-85") (pin "2") (pinfunction "2_2") (pintype "passive"))
    )
    (net (code "71") (name "Net-(C6D78-85-Pad3)") (class "Default")
      (node (ref "C6D78-85") (pin "3") (pinfunction "3_3") (pintype "passive"))
      (node (ref "C6D78-85") (pin "4") (pinfunction "4_4") (pintype "passive"))
    )
    (net (code "72") (name "Net-(C6D78-85-Pad5)") (class "Default")
      (node (ref "C6D78-85") (pin "5") (pinfunction "5_5") (pintype "passive"))
      (node (ref "C6D78-85") (pin "6") (pinfunction "6_6") (pintype "passive"))
    )
    (net (code "73") (name "Net-(C6D78-85-Pad7)") (class "Default")
      (node (ref "C6D78-85") (pin "7") (pinfunction "7_7") (pintype "passive"))
      (node (ref "C6D78-85") (pin "8") (pinfunction "8_8") (pintype "passive"))
    )
    (net (code "74") (name "Net-(C6D78-85-Pad10)") (class "Default")
      (node (ref "C6D78-85") (pin "10") (pinfunction "10_10") (pintype "passive"))
      (node (ref "C6D78-85") (pin "9") (pinfunction "9_9") (pintype "passive"))
    )
    (net (code "75") (name "Net-(C6D78-85-Pad11)") (class "Default")
      (node (ref "C6D78-85") (pin "11") (pinfunction "11_11") (pintype "passive"))
      (node (ref "C6D78-85") (pin "12") (pinfunction "12_12") (pintype "passive"))
    )
    (net (code "76") (name "Net-(C6D78-85-Pad13)") (class "Default")
      (node (ref "C6D78-85") (pin "13") (pinfunction "13_13") (pintype "passive"))
      (node (ref "C6D78-85") (pin "14") (pinfunction "14_14") (pintype "passive"))
    )
    (net (code "77") (name "Net-(C6D78-85-Pad15)") (class "Default")
      (node (ref "C6D78-85") (pin "15") (pinfunction "15_15") (pintype "passive"))
      (node (ref "C6D78-85") (pin "16") (pinfunction "16_16") (pintype "passive"))
    )
    (net (code "78") (name "Net-(INU-5)") (class "Default")
      (node (ref "C6D22-37") (pin "12") (pinfunction "12_12") (pintype "passive"))
      (node (ref "INU") (pin "D6") (pinfunction "5_D6") (pintype "passive"))
    )
    (net (code "79") (name "Net-(INU-6)") (class "Default")
      (node (ref "C6D8-13") (pin "3") (pinfunction "3_3") (pintype "passive"))
      (node (ref "ICSP") (pin "3") (pinfunction "3_3") (pintype "passive"))
      (node (ref "INU") (pin "D5") (pinfunction "6_D5") (pintype "passive"))
      (node (ref "JP2") (pin "1") (pinfunction "1_1") (pintype "passive"))
      (node (ref "MOUSE") (pin "7") (pinfunction "7_7") (pintype "passive"))
    )
    (net (code "80") (name "Net-(INU-7)") (class "Default")
      (node (ref "C6D8-13") (pin "4") (pinfunction "4_4") (pintype "passive"))
      (node (ref "ICSP") (pin "1") (pinfunction "1_1") (pintype "passive"))
      (node (ref "INU") (pin "D4") (pinfunction "7_D4") (pintype "passive"))
      (node (ref "JP3") (pin "1") (pinfunction "1_1") (pintype "passive"))
      (node (ref "MOUSE") (pin "5") (pinfunction "5_5") (pintype "passive"))
    )
    (net (code "81") (name "Net-(JP4-1)") (class "Default")
      (node (ref "C6D22-37") (pin "10") (pinfunction "10_10") (pintype "passive"))
      (node (ref "JP4") (pin "P$1") (pinfunction "1_P$1") (pintype "passive"))
    )
    (net (code "82") (name "Net-(JP4-2)") (class "Default")
      (node (ref "C6D22-37") (pin "8") (pinfunction "8_8") (pintype "passive"))
      (node (ref "JP4") (pin "P$2") (pinfunction "2_P$2") (pintype "passive"))
    )
    (net (code "83") (name "Net-(JP4-3)") (class "Default")
      (node (ref "C6D22-37") (pin "6") (pinfunction "6_6") (pintype "passive"))
      (node (ref "JP4") (pin "P$3") (pinfunction "3_P$3") (pintype "passive"))
    )
    (net (code "84") (name "Net-(JP4-4)") (class "Default")
      (node (ref "C6D22-37") (pin "4") (pinfunction "4_4") (pintype "passive"))
      (node (ref "JP4") (pin "P$4") (pinfunction "4_P$4") (pintype "passive"))
    )
    (net (code "85") (name "Net-(JP4-5)") (class "Default")
      (node (ref "C6D22-37") (pin "2") (pinfunction "2_2") (pintype "passive"))
      (node (ref "JP4") (pin "P$5") (pinfunction "5_P$5") (pintype "passive"))
    )
    (net (code "86") (name "Net-(JP4-8)") (class "Default")
      (node (ref "C6D38-53") (pin "6") (pinfunction "6_6") (pintype "passive"))
      (node (ref "JP4") (pin "P$8") (pinfunction "8_P$8") (pintype "passive"))
    )
    (net (code "87") (name "Net-(R1B-1)") (class "Default")
      (node (ref "R1B") (pin "P$1") (pinfunction "1_P$1") (pintype "passive"))
      (node (ref "R2B") (pin "P$3") (pinfunction "3_P$3") (pintype "passive"))
      (node (ref "R3B") (pin "P$3") (pinfunction "3_P$3") (pintype "passive"))
    )
    (net (code "88") (name "Net-(R1B-2)") (class "Default")
      (node (ref "R1B") (pin "P$2") (pinfunction "2_P$2") (pintype "passive"))
      (node (ref "R2B") (pin "P$4") (pinfunction "4_P$4") (pintype "passive"))
      (node (ref "R3B") (pin "P$4") (pinfunction "4_P$4") (pintype "passive"))
    )
    (net (code "89") (name "Net-(R1B-3)") (class "Default")
      (node (ref "R1B") (pin "P$3") (pinfunction "3_P$3") (pintype "passive"))
      (node (ref "R2B") (pin "P$5") (pinfunction "5_P$5") (pintype "passive"))
      (node (ref "R3B") (pin "P$5") (pinfunction "5_P$5") (pintype "passive"))
    )
    (net (code "90") (name "Net-(R1B-4)") (class "Default")
      (node (ref "R1B") (pin "P$4") (pinfunction "4_P$4") (pintype "passive"))
      (node (ref "R2B") (pin "P$6") (pinfunction "6_P$6") (pintype "passive"))
      (node (ref "R3B") (pin "P$6") (pinfunction "6_P$6") (pintype "passive"))
    )
    (net (code "91") (name "Net-(R1B-5)") (class "Default")
      (node (ref "R1B") (pin "P$5") (pinfunction "5_P$5") (pintype "passive"))
      (node (ref "R2B") (pin "P$7") (pinfunction "7_P$7") (pintype "passive"))
      (node (ref "R3B") (pin "P$7") (pinfunction "7_P$7") (pintype "passive"))
    )
    (net (code "92") (name "Net-(R1B-6)") (class "Default")
      (node (ref "R1B") (pin "P$6") (pinfunction "6_P$6") (pintype "passive"))
      (node (ref "R2B") (pin "P$8") (pinfunction "8_P$8") (pintype "passive"))
      (node (ref "R3B") (pin "P$8") (pinfunction "8_P$8") (pintype "passive"))
    )
    (net (code "93") (name "Net-(R2A-1)") (class "Default")
      (node (ref "R2A") (pin "P$1") (pinfunction "1_P$1") (pintype "passive"))
      (node (ref "R3A") (pin "P$1") (pinfunction "1_P$1") (pintype "passive"))
    )
    (net (code "94") (name "Net-(R2A-2)") (class "Default")
      (node (ref "R2A") (pin "P$2") (pinfunction "2_P$2") (pintype "passive"))
      (node (ref "R3A") (pin "P$2") (pinfunction "2_P$2") (pintype "passive"))
    )
    (net (code "95") (name "Net-(R2A-3)") (class "Default")
      (node (ref "R2A") (pin "P$3") (pinfunction "3_P$3") (pintype "passive"))
      (node (ref "R3A") (pin "P$3") (pinfunction "3_P$3") (pintype "passive"))
    )
    (net (code "96") (name "Net-(R2A-4)") (class "Default")
      (node (ref "R2A") (pin "P$4") (pinfunction "4_P$4") (pintype "passive"))
      (node (ref "R3A") (pin "P$4") (pinfunction "4_P$4") (pintype "passive"))
    )
    (net (code "97") (name "Net-(R2A-5)") (class "Default")
      (node (ref "R2A") (pin "P$5") (pinfunction "5_P$5") (pintype "passive"))
      (node (ref "R3A") (pin "P$5") (pinfunction "5_P$5") (pintype "passive"))
    )
    (net (code "98") (name "Net-(R2A-6)") (class "Default")
      (node (ref "R2A") (pin "P$6") (pinfunction "6_P$6") (pintype "passive"))
      (node (ref "R3A") (pin "P$6") (pinfunction "6_P$6") (pintype "passive"))
    )
    (net (code "99") (name "Net-(R2B-1)") (class "Default")
      (node (ref "R2B") (pin "P$1") (pinfunction "1_P$1") (pintype "passive"))
      (node (ref "R3B") (pin "P$1") (pinfunction "1_P$1") (pintype "passive"))
    )
    (net (code "100") (name "Net-(R2B-2)") (class "Default")
      (node (ref "R2B") (pin "P$2") (pinfunction "2_P$2") (pintype "passive"))
      (node (ref "R3B") (pin "P$2") (pinfunction "2_P$2") (pintype "passive"))
    )
    (net (code "101") (name "Net-(R4A-1)") (class "Default")
      (node (ref "R4A") (pin "P$1") (pinfunction "1_P$1") (pintype "passive"))
      (node (ref "R5A") (pin "P$1") (pinfunction "1_P$1") (pintype "passive"))
      (node (ref "R6A") (pin "P$1") (pinfunction "1_P$1") (pintype "passive"))
    )
    (net (code "102") (name "Net-(R4A-2)") (class "Default")
      (node (ref "R4A") (pin "P$2") (pinfunction "2_P$2") (pintype "passive"))
      (node (ref "R5A") (pin "P$2") (pinfunction "2_P$2") (pintype "passive"))
      (node (ref "R6A") (pin "P$2") (pinfunction "2_P$2") (pintype "passive"))
    )
    (net (code "103") (name "Net-(R4A-3)") (class "Default")
      (node (ref "R4A") (pin "P$3") (pinfunction "3_P$3") (pintype "passive"))
      (node (ref "R5A") (pin "P$3") (pinfunction "3_P$3") (pintype "passive"))
      (node (ref "R6A") (pin "P$3") (pinfunction "3_P$3") (pintype "passive"))
    )
    (net (code "104") (name "Net-(R4A-4)") (class "Default")
      (node (ref "R4A") (pin "P$4") (pinfunction "4_P$4") (pintype "passive"))
      (node (ref "R5A") (pin "P$4") (pinfunction "4_P$4") (pintype "passive"))
      (node (ref "R6A") (pin "P$4") (pinfunction "4_P$4") (pintype "passive"))
    )
    (net (code "105") (name "Net-(R4A-5)") (class "Default")
      (node (ref "R4A") (pin "P$5") (pinfunction "5_P$5") (pintype "passive"))
      (node (ref "R5A") (pin "P$5") (pinfunction "5_P$5") (pintype "passive"))
      (node (ref "R6A") (pin "P$5") (pinfunction "5_P$5") (pintype "passive"))
    )
    (net (code "106") (name "Net-(R4A-6)") (class "Default")
      (node (ref "R4A") (pin "P$6") (pinfunction "6_P$6") (pintype "passive"))
      (node (ref "R5A") (pin "P$6") (pinfunction "6_P$6") (pintype "passive"))
      (node (ref "R6A") (pin "P$6") (pinfunction "6_P$6") (pintype "passive"))
    )
    (net (code "107") (name "Net-(R4B-1)") (class "Default")
      (node (ref "R4B") (pin "P$1") (pinfunction "1_P$1") (pintype "passive"))
      (node (ref "R5B") (pin "P$1") (pinfunction "1_P$1") (pintype "passive"))
      (node (ref "R6B") (pin "P$1") (pinfunction "1_P$1") (pintype "passive"))
    )
    (net (code "108") (name "Net-(R4B-2)") (class "Default")
      (node (ref "R4B") (pin "P$2") (pinfunction "2_P$2") (pintype "passive"))
      (node (ref "R5B") (pin "P$2") (pinfunction "2_P$2") (pintype "passive"))
      (node (ref "R6B") (pin "P$2") (pinfunction "2_P$2") (pintype "passive"))
    )
    (net (code "109") (name "Net-(R4B-3)") (class "Default")
      (node (ref "R4B") (pin "P$3") (pinfunction "3_P$3") (pintype "passive"))
      (node (ref "R5B") (pin "P$3") (pinfunction "3_P$3") (pintype "passive"))
      (node (ref "R6B") (pin "P$3") (pinfunction "3_P$3") (pintype "passive"))
    )
    (net (code "110") (name "Net-(R4B-4)") (class "Default")
      (node (ref "R4B") (pin "P$4") (pinfunction "4_P$4") (pintype "passive"))
      (node (ref "R5B") (pin "P$4") (pinfunction "4_P$4") (pintype "passive"))
      (node (ref "R6B") (pin "P$4") (pinfunction "4_P$4") (pintype "passive"))
    )
    (net (code "111") (name "Net-(R4B-5)") (class "Default")
      (node (ref "R4B") (pin "P$5") (pinfunction "5_P$5") (pintype "passive"))
      (node (ref "R5B") (pin "P$5") (pinfunction "5_P$5") (pintype "passive"))
      (node (ref "R6B") (pin "P$5") (pinfunction "5_P$5") (pintype "passive"))
    )
    (net (code "112") (name "Net-(R4B-6)") (class "Default")
      (node (ref "R4B") (pin "P$6") (pinfunction "6_P$6") (pintype "passive"))
      (node (ref "R5B") (pin "P$6") (pinfunction "6_P$6") (pintype "passive"))
      (node (ref "R6B") (pin "P$6") (pinfunction "6_P$6") (pintype "passive"))
    )
    (net (code "113") (name "Net-(R4B-7)") (class "Default")
      (node (ref "R4B") (pin "P$7") (pinfunction "7_P$7") (pintype "passive"))
      (node (ref "R5B") (pin "P$7") (pinfunction "7_P$7") (pintype "passive"))
      (node (ref "R6B") (pin "P$7") (pinfunction "7_P$7") (pintype "passive"))
    )
    (net (code "114") (name "Net-(R4B-8)") (class "Default")
      (node (ref "R4B") (pin "P$8") (pinfunction "8_P$8") (pintype "passive"))
      (node (ref "R5B") (pin "P$8") (pinfunction "8_P$8") (pintype "passive"))
      (node (ref "R6B") (pin "P$8") (pinfunction "8_P$8") (pintype "passive"))
    )
    (net (code "115") (name "Net-(RL1A-1)") (class "Default")
      (node (ref "R3") (pin "1") (pinfunction "1_1") (pintype "passive"))
      (node (ref "RL1") (pin "COIL1") (pinfunction "1_COIL1") (pintype "passive"))
    )
    (net (code "116") (name "Net-(X2-1)") (class "Default")
      (node (ref "C6D0-7") (pin "5") (pinfunction "5_5") (pintype "passive"))
      (node (ref "R1") (pin "1") (pinfunction "1_1") (pintype "passive"))
      (node (ref "X1") (pin "14") (pinfunction "14_14") (pintype "passive"))
      (node (ref "X2") (pin "P$1") (pinfunction "1_P$1") (pintype "passive"))
    )
    (net (code "117") (name "Net-(X3-1)") (class "Default")
      (node (ref "C6D0-7") (pin "6") (pinfunction "6_6") (pintype "passive"))
      (node (ref "R2") (pin "1") (pinfunction "1_1") (pintype "passive"))
      (node (ref "X1") (pin "21") (pinfunction "21_21") (pintype "passive"))
      (node (ref "X3") (pin "P$1") (pinfunction "1_P$1") (pintype "passive"))
    )
    (net (code "118") (name "unconnected-(C5A-Pad4)") (class "Default")
      (node (ref "C5A") (pin "4") (pinfunction "4_4") (pintype "passive"))
    )
    (net (code "119") (name "unconnected-(C5A-Pad14)") (class "Default")
      (node (ref "C5A") (pin "14") (pinfunction "14_14") (pintype "passive"))
    )
    (net (code "120") (name "unconnected-(C6D0-7-Pad1)") (class "Default")
      (node (ref "C6D0-7") (pin "1") (pinfunction "1_1") (pintype "passive"))
    )
    (net (code "121") (name "unconnected-(C6D8-13-Pad7)") (class "Default")
      (node (ref "C6D8-13") (pin "7") (pinfunction "7_7") (pintype "passive"))
    )
    (net (code "122") (name "unconnected-(INU-4-Pad3V)") (class "Default")
      (node (ref "INU") (pin "3V") (pinfunction "4_3V") (pintype "passive"))
    )
    (net (code "123") (name "unconnected-(INU-11-PadPGM)") (class "Default")
      (node (ref "INU") (pin "PGM") (pinfunction "11_PGM") (pintype "passive"))
    )
    (net (code "124") (name "unconnected-(POWER-Pad7)") (class "Default")
      (node (ref "POWER") (pin "7") (pinfunction "7_7") (pintype "passive"))
    )
    (net (code "125") (name "unconnected-(POWER-Pad8)") (class "Default")
      (node (ref "POWER") (pin "8") (pinfunction "8_8") (pintype "passive"))
    )
    (net (code "126") (name "unconnected-(RL1A-3-PadCOM1)") (class "Default")
      (node (ref "RL1") (pin "COM1") (pinfunction "3_COM1") (pintype "passive"))
    )
  )
)
